# MCX_Isolated_Mezzanine.net
KiCad netlist of a schematic drawn in Altium Designer
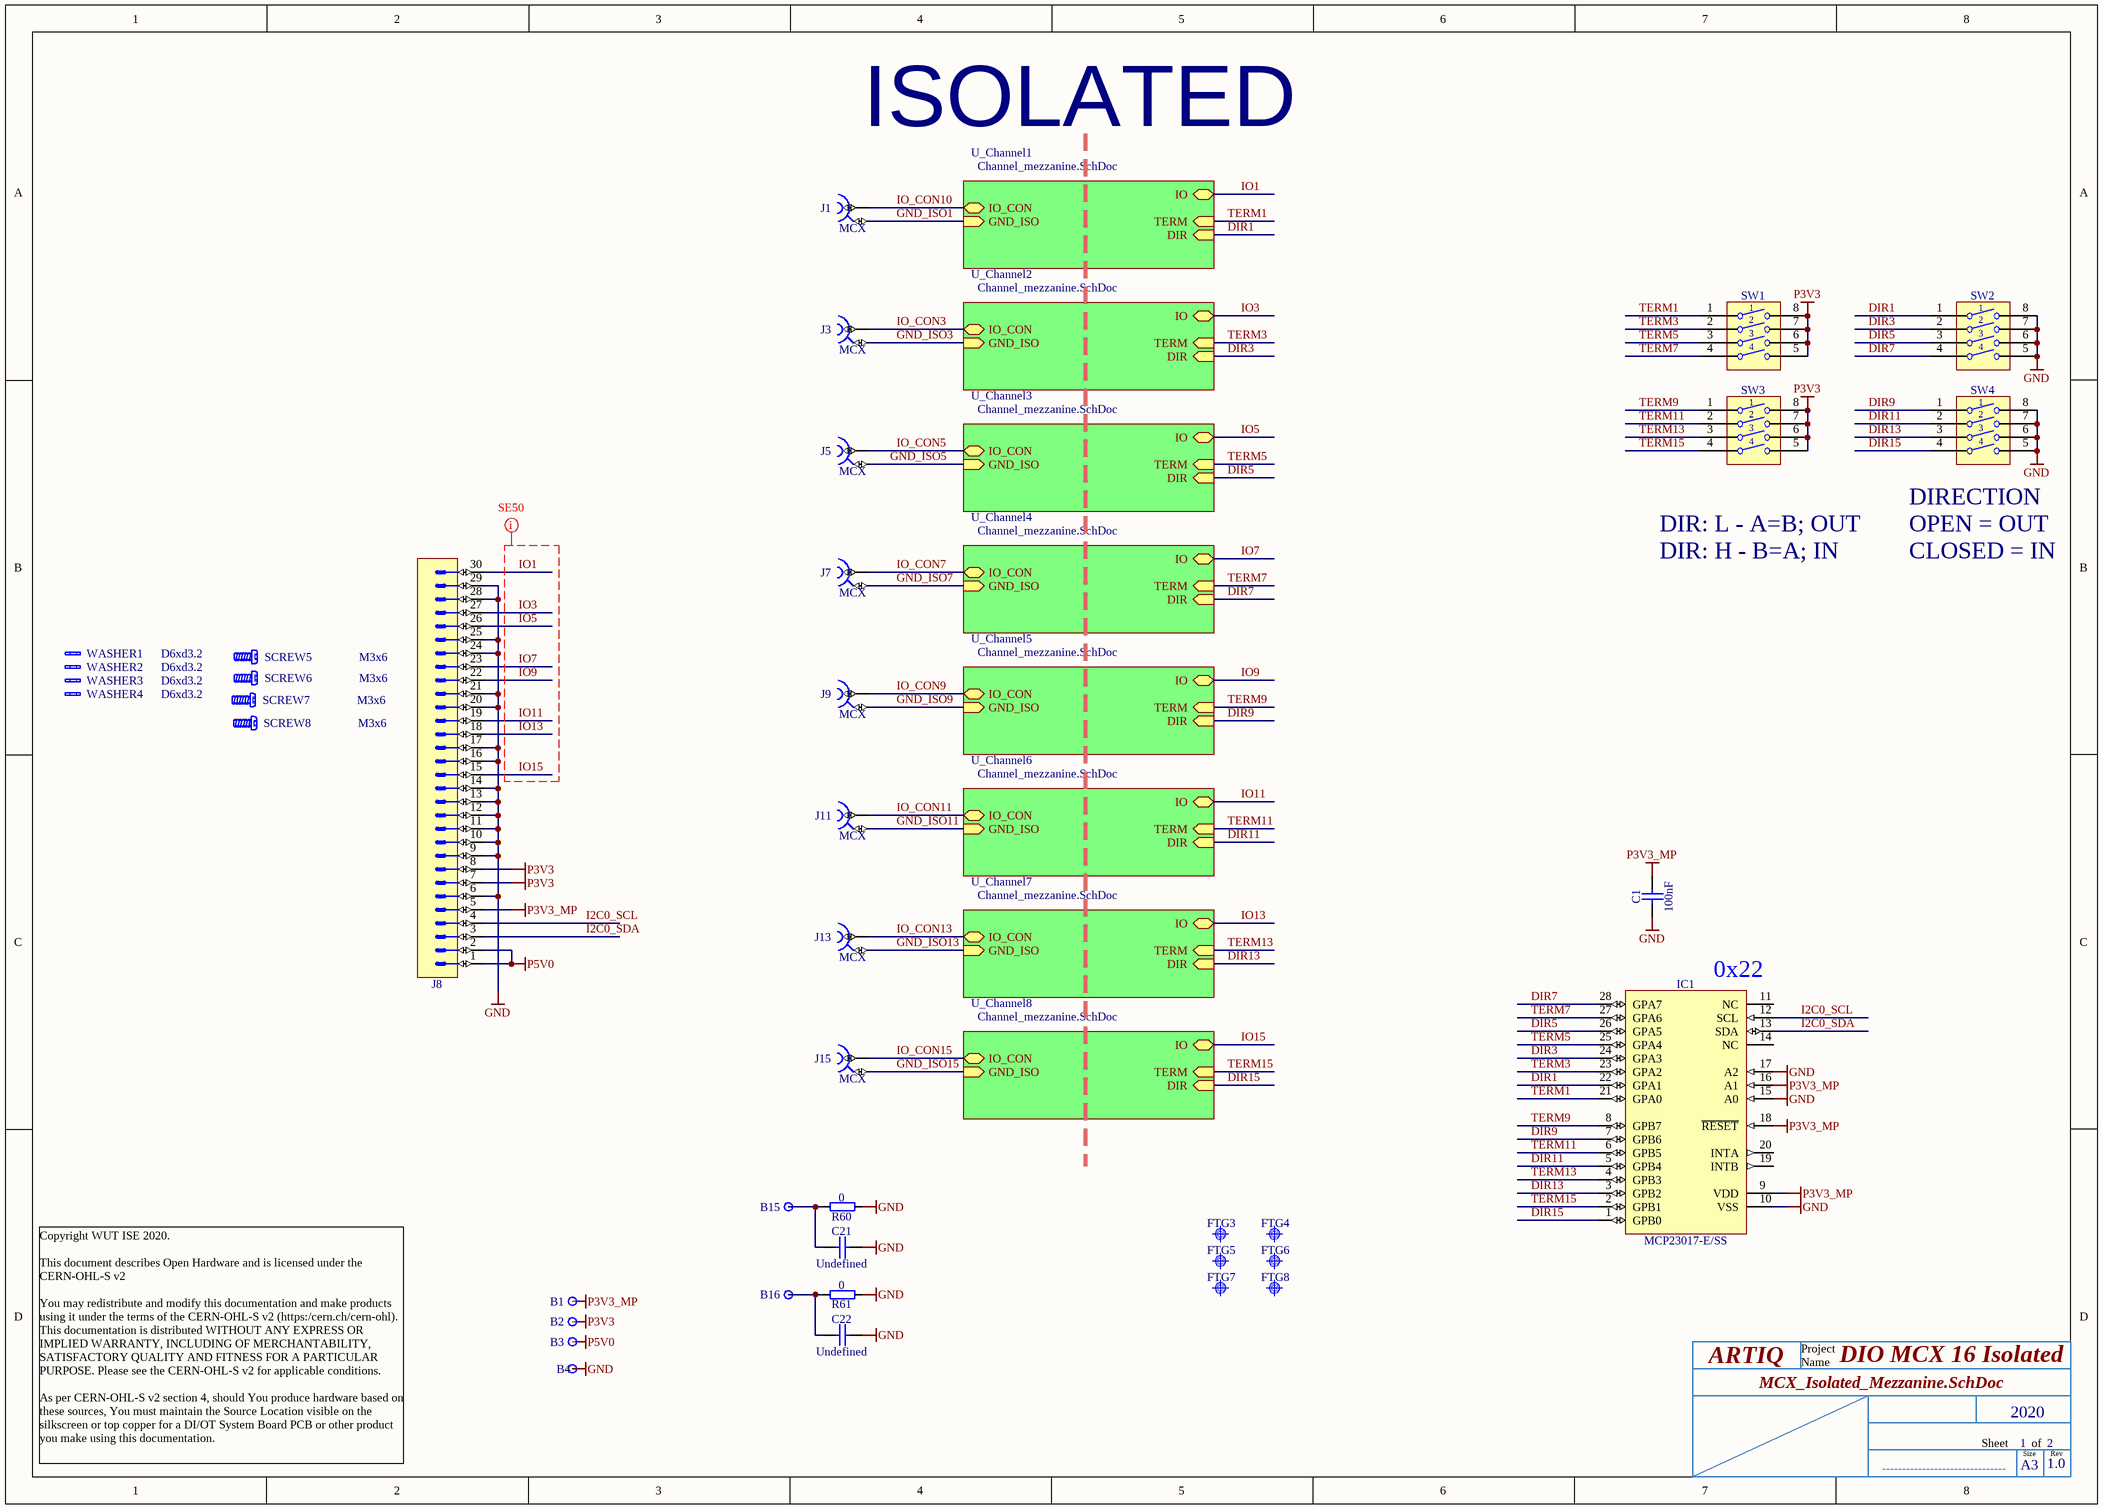
[diagram p0: MCX_Isolated_Mezzanine.SchDoc]

(export (version "E")
  (design (tool "Eeschema 10.0.6"))
  (components
    (comp (ref "B1")
      (value "Plated Hole")
      (footprint "c130h60")
      (description "Single Terminal Socket")
      (fields (field (name "PART NUMBER") "PLATED_HOLE0.6_PAD1.3") (field (name "AUTHOR") "CERN DEM MR"))
      (libsource (lib "Eletro-mechanical") (part "Single Terminal Socket"))
    )
    (comp (ref "B2")
      (value "Plated Hole")
      (footprint "c130h60")
      (description "Single Terminal Socket")
      (fields (field (name "PART NUMBER") "PLATED_HOLE0.6_PAD1.3") (field (name "AUTHOR") "CERN DEM MR"))
      (libsource (lib "Eletro-mechanical") (part "Single Terminal Socket"))
    )
    (comp (ref "B3")
      (value "Plated Hole")
      (footprint "c130h60")
      (description "Single Terminal Socket")
      (fields (field (name "PART NUMBER") "PLATED_HOLE0.6_PAD1.3") (field (name "AUTHOR") "CERN DEM MR"))
      (libsource (lib "Eletro-mechanical") (part "Single Terminal Socket"))
    )
    (comp (ref "B4")
      (value "Plated Hole")
      (footprint "c130h60")
      (description "Single Terminal Socket")
      (fields (field (name "PART NUMBER") "PLATED_HOLE0.6_PAD1.3") (field (name "AUTHOR") "CERN DEM MR"))
      (libsource (lib "Eletro-mechanical") (part "Single Terminal Socket"))
    )
    (comp (ref "B15")
      (value "Plated Hole")
      (footprint "MTG270_500")
      (description "Single Terminal Socket")
      (fields (field (name "PART NUMBER") "PLATED_HOLE2.7_PAD5.0") (field (name "AUTHOR") "CERN DEM JMW"))
      (libsource (lib "Eletro-mechanical") (part "Single Terminal Socket"))
    )
    (comp (ref "B16")
      (value "Plated Hole")
      (footprint "MTG270_500")
      (description "Single Terminal Socket")
      (fields (field (name "PART NUMBER") "PLATED_HOLE2.7_PAD5.0") (field (name "AUTHOR") "CERN DEM JMW"))
      (libsource (lib "Eletro-mechanical") (part "Single Terminal Socket"))
    )
    (comp (ref "C1")
      (value "100nF")
      (footprint "CAPC1005X55N")
      (description "Non-polarised capacitor")
      (fields
        (field (name "PART NUMBER") "CC0402_100NF_50V_10%_X7R")
        (field (name "VOLTAGE") "50V")
        (field (name "AUTHOR") "CERN DEM MR")
      )
      (libsource (lib "Capacitors") (part "Capacitor - non polarized"))
    )
    (comp (ref "C21")
      (value "Undefined")
      (footprint "CAPC2012X135N")
      (description "Non-polarised capacitor")
      (fields (field (name "PART NUMBER") "CC0805_NO-VALUE") (field (name "AUTHOR") "CERN DEM JLC"))
      (libsource (lib "Capacitors") (part "Capacitor - non polarized"))
    )
    (comp (ref "C22")
      (value "Undefined")
      (footprint "CAPC2012X135N")
      (description "Non-polarised capacitor")
      (fields (field (name "PART NUMBER") "CC0805_NO-VALUE") (field (name "AUTHOR") "CERN DEM JLC"))
      (libsource (lib "Capacitors") (part "Capacitor - non polarized"))
    )
    (comp (ref "FTG3")
      (value "Use only in PCB")
      (footprint "FIDUCIAL_TOP_S100-200")
      (description "Fiducial Target")
      (fields (field (name "PART NUMBER") "FIDUCIAL_TARGET_S100-200") (field (name "AUTHOR") "CERN DEM JLC"))
      (libsource (lib "Eletro-mechanical") (part "Fiducial Target"))
    )
    (comp (ref "FTG4")
      (value "Use only in PCB")
      (footprint "FIDUCIAL_TOP_C100-200")
      (description "Fiducial Target")
      (fields (field (name "PART NUMBER") "FIDUCIAL_TARGET_C100-200") (field (name "AUTHOR") "CERN DEM JLC"))
      (libsource (lib "Eletro-mechanical") (part "Fiducial Target"))
    )
    (comp (ref "FTG5")
      (value "Use only in PCB")
      (footprint "FIDUCIAL_TOP_S100-200")
      (description "Fiducial Target")
      (fields (field (name "PART NUMBER") "FIDUCIAL_TARGET_S100-200") (field (name "AUTHOR") "CERN DEM JLC"))
      (libsource (lib "Eletro-mechanical") (part "Fiducial Target"))
    )
    (comp (ref "FTG6")
      (value "Use only in PCB")
      (footprint "FIDUCIAL_TOP_C100-200")
      (description "Fiducial Target")
      (fields (field (name "PART NUMBER") "FIDUCIAL_TARGET_C100-200") (field (name "AUTHOR") "CERN DEM JLC"))
      (libsource (lib "Eletro-mechanical") (part "Fiducial Target"))
    )
    (comp (ref "FTG7")
      (value "Use only in PCB")
      (footprint "FIDUCIAL_TOP_C100-200")
      (description "Fiducial Target")
      (fields (field (name "PART NUMBER") "FIDUCIAL_TARGET_C100-200") (field (name "AUTHOR") "CERN DEM JLC"))
      (libsource (lib "Eletro-mechanical") (part "Fiducial Target"))
    )
    (comp (ref "FTG8")
      (value "Use only in PCB")
      (footprint "FIDUCIAL_TOP_S100-200")
      (description "Fiducial Target")
      (fields (field (name "PART NUMBER") "FIDUCIAL_TARGET_S100-200") (field (name "AUTHOR") "CERN DEM JLC"))
      (libsource (lib "Eletro-mechanical") (part "Fiducial Target"))
    )
    (comp (ref "IC1")
      (value "MCP23017-E/SS")
      (footprint "SOP65P780X200-28N")
      (description "16-bit I/O Port Expander With Serial Interface")
      (fields (field (name "MANUFACTURER") "MICROCHIP TECHNOLOGY") (field (name "AUTHOR") "CERN DEM JLC"))
      (libsource (lib "ICs And Semiconductors") (part "MCP23017-E/SS"))
    )
    (comp (ref "J1")
      (value "MCX")
      (footprint "BEL_133-3701-801")
      (fields
        (field (name "PART NUMBER") "BELFUSE_133-3701-801")
        (field (name "MANUFACTURER") "BEL")
        (field (name "MANUFACTURER PART NUMBER") "133-3701-801")
        (field (name "AUTHOR") "CERN DEM MR")
      )
      (libsource (lib "Connectors") (part "Coax_1Female_1Shield"))
    )
    (comp (ref "J3")
      (value "MCX")
      (footprint "BEL_133-3701-801")
      (fields
        (field (name "PART NUMBER") "BELFUSE_133-3701-801")
        (field (name "MANUFACTURER") "BEL")
        (field (name "MANUFACTURER PART NUMBER") "133-3701-801")
        (field (name "AUTHOR") "CERN DEM MR")
      )
      (libsource (lib "Connectors") (part "Coax_1Female_1Shield"))
    )
    (comp (ref "J5")
      (value "MCX")
      (footprint "BEL_133-3701-801")
      (fields
        (field (name "PART NUMBER") "BELFUSE_133-3701-801")
        (field (name "MANUFACTURER") "BEL")
        (field (name "MANUFACTURER PART NUMBER") "133-3701-801")
        (field (name "AUTHOR") "CERN DEM MR")
      )
      (libsource (lib "Connectors") (part "Coax_1Female_1Shield"))
    )
    (comp (ref "J7")
      (value "MCX")
      (footprint "BEL_133-3701-801")
      (fields
        (field (name "PART NUMBER") "BELFUSE_133-3701-801")
        (field (name "MANUFACTURER") "BEL")
        (field (name "MANUFACTURER PART NUMBER") "133-3701-801")
        (field (name "AUTHOR") "CERN DEM MR")
      )
      (libsource (lib "Connectors") (part "Coax_1Female_1Shield"))
    )
    (comp (ref "J8")
      (value "AMPMODU")
      (footprint "TYCO_1-215307-5")
      (description "Connector 2.54mm, 30 pin female, vertical, 7mm, AMPMODU HV-100/HV-190")
      (fields
        (field (name "PART NUMBER") "TYCO_1-215307-5")
        (field (name "MANUFACTURER") "TYCO ELECTRONICS")
        (field (name "AUTHOR") "GK")
      )
      (libsource (lib "LIBRARY_SCH") (part "CON_2x15_2.54_female_V_mirror"))
    )
    (comp (ref "J9")
      (value "MCX")
      (footprint "BEL_133-3701-801")
      (fields
        (field (name "PART NUMBER") "BELFUSE_133-3701-801")
        (field (name "MANUFACTURER") "BEL")
        (field (name "MANUFACTURER PART NUMBER") "133-3701-801")
        (field (name "AUTHOR") "CERN DEM MR")
      )
      (libsource (lib "Connectors") (part "Coax_1Female_1Shield"))
    )
    (comp (ref "J11")
      (value "MCX")
      (footprint "BEL_133-3701-801")
      (fields
        (field (name "PART NUMBER") "BELFUSE_133-3701-801")
        (field (name "MANUFACTURER") "BEL")
        (field (name "MANUFACTURER PART NUMBER") "133-3701-801")
        (field (name "AUTHOR") "CERN DEM MR")
      )
      (libsource (lib "Connectors") (part "Coax_1Female_1Shield"))
    )
    (comp (ref "J13")
      (value "MCX")
      (footprint "BEL_133-3701-801")
      (fields
        (field (name "PART NUMBER") "BELFUSE_133-3701-801")
        (field (name "MANUFACTURER") "BEL")
        (field (name "MANUFACTURER PART NUMBER") "133-3701-801")
        (field (name "AUTHOR") "CERN DEM MR")
      )
      (libsource (lib "Connectors") (part "Coax_1Female_1Shield"))
    )
    (comp (ref "J15")
      (value "MCX")
      (footprint "BEL_133-3701-801")
      (fields
        (field (name "PART NUMBER") "BELFUSE_133-3701-801")
        (field (name "MANUFACTURER") "BEL")
        (field (name "MANUFACTURER PART NUMBER") "133-3701-801")
        (field (name "AUTHOR") "CERN DEM MR")
      )
      (libsource (lib "Connectors") (part "Coax_1Female_1Shield"))
    )
    (comp (ref "R60")
      (value "0")
      (footprint "RESC1608X55N")
      (description "Resistor")
      (fields
        (field (name "PART NUMBER") "R0603_0R_JUMPER")
        (field (name "MANUFACTURER") "GENERIC")
        (field (name "AUTHOR") "CERN DEM JLC")
      )
      (libsource (lib "Resistors") (part "Resistor"))
    )
    (comp (ref "R61")
      (value "0")
      (footprint "RESC1608X55N")
      (description "Resistor")
      (fields
        (field (name "PART NUMBER") "R0603_0R_JUMPER")
        (field (name "MANUFACTURER") "GENERIC")
        (field (name "AUTHOR") "CERN DEM JLC")
      )
      (libsource (lib "Resistors") (part "Resistor"))
    )
    (comp (ref "SCREW5")
      (value "M3x6")
      (footprint "BOSSARD_BN5687-3061605_v")
      (description "Screw")
      (fields
        (field (name "PART NUMBER") "BOSSARD_BN5687-3061605_v")
        (field (name "MANUFACTURER") "BOSSARD")
        (field (name "AUTHOR") "CERN DEM JLC")
      )
      (libsource (lib "Eletro-mechanical") (part "Screw"))
    )
    (comp (ref "SCREW6")
      (value "M3x6")
      (footprint "BOSSARD_BN5687-3061605_v")
      (description "Screw")
      (fields
        (field (name "PART NUMBER") "BOSSARD_BN5687-3061605_v")
        (field (name "MANUFACTURER") "BOSSARD")
        (field (name "AUTHOR") "CERN DEM JLC")
      )
      (libsource (lib "Eletro-mechanical") (part "Screw"))
    )
    (comp (ref "SCREW7")
      (value "M3x6")
      (footprint "BOSSARD_BN5687-3061605_v")
      (description "Screw")
      (fields
        (field (name "PART NUMBER") "BOSSARD_BN5687-3061605_v")
        (field (name "MANUFACTURER") "BOSSARD")
        (field (name "AUTHOR") "CERN DEM JLC")
      )
      (libsource (lib "Eletro-mechanical") (part "Screw"))
    )
    (comp (ref "SCREW8")
      (value "M3x6")
      (footprint "BOSSARD_BN5687-3061605_v")
      (description "Screw")
      (fields
        (field (name "PART NUMBER") "BOSSARD_BN5687-3061605_v")
        (field (name "MANUFACTURER") "BOSSARD")
        (field (name "AUTHOR") "CERN DEM JLC")
      )
      (libsource (lib "Eletro-mechanical") (part "Screw"))
    )
    (comp (ref "SW1")
      (value "Switch")
      (footprint "SW_OMRON_A6S-4102-H")
      (description "4 Ways SPST DIP Switch")
      (fields
        (field (name "PART NUMBER") "SW_OMRON_A6S-4102-H")
        (field (name "MANUFACTURER") "OMRON")
        (field (name "AUTHOR") "CERN DEM JMW")
      )
      (libsource (lib "Eletro-mechanical") (part "SW 4x SPST DIP Switch"))
    )
    (comp (ref "SW2")
      (value "Switch")
      (footprint "SW_OMRON_A6S-4102-H")
      (description "4 Ways SPST DIP Switch")
      (fields
        (field (name "PART NUMBER") "SW_OMRON_A6S-4102-H")
        (field (name "MANUFACTURER") "OMRON")
        (field (name "AUTHOR") "CERN DEM JMW")
      )
      (libsource (lib "Eletro-mechanical") (part "SW 4x SPST DIP Switch"))
    )
    (comp (ref "SW3")
      (value "Switch")
      (footprint "SW_OMRON_A6S-4102-H")
      (description "4 Ways SPST DIP Switch")
      (fields
        (field (name "PART NUMBER") "SW_OMRON_A6S-4102-H")
        (field (name "MANUFACTURER") "OMRON")
        (field (name "AUTHOR") "CERN DEM JMW")
      )
      (libsource (lib "Eletro-mechanical") (part "SW 4x SPST DIP Switch"))
    )
    (comp (ref "SW4")
      (value "Switch")
      (footprint "SW_OMRON_A6S-4102-H")
      (description "4 Ways SPST DIP Switch")
      (fields
        (field (name "PART NUMBER") "SW_OMRON_A6S-4102-H")
        (field (name "MANUFACTURER") "OMRON")
        (field (name "AUTHOR") "CERN DEM JMW")
      )
      (libsource (lib "Eletro-mechanical") (part "SW 4x SPST DIP Switch"))
    )
    (comp (ref "WASHER1")
      (value "D6xd3.2")
      (footprint "BOSSARD_B3/6/0.3/BN1976_v")
      (description "Washer, M3x0.3x6")
      (fields
        (field (name "PART NUMBER") "BOSSARD_B3/6/0.3/BN1976")
        (field (name "MANUFACTURER") "BOSSARD")
        (field (name "AUTHOR") "GK")
      )
      (libsource (lib "Mechanical") (part "MECH_Washer_M3x0.3x6"))
    )
    (comp (ref "WASHER2")
      (value "D6xd3.2")
      (footprint "BOSSARD_B3/6/0.3/BN1976_v")
      (description "Washer, M3x0.3x6")
      (fields
        (field (name "PART NUMBER") "BOSSARD_B3/6/0.3/BN1976")
        (field (name "MANUFACTURER") "BOSSARD")
        (field (name "AUTHOR") "GK")
      )
      (libsource (lib "Mechanical") (part "MECH_Washer_M3x0.3x6"))
    )
    (comp (ref "WASHER3")
      (value "D6xd3.2")
      (footprint "BOSSARD_B3/6/0.3/BN1976_v")
      (description "Washer, M3x0.3x6")
      (fields
        (field (name "PART NUMBER") "BOSSARD_B3/6/0.3/BN1976")
        (field (name "MANUFACTURER") "BOSSARD")
        (field (name "AUTHOR") "GK")
      )
      (libsource (lib "Mechanical") (part "MECH_Washer_M3x0.3x6"))
    )
    (comp (ref "WASHER4")
      (value "D6xd3.2")
      (footprint "BOSSARD_B3/6/0.3/BN1976_v")
      (description "Washer, M3x0.3x6")
      (fields
        (field (name "PART NUMBER") "BOSSARD_B3/6/0.3/BN1976")
        (field (name "MANUFACTURER") "BOSSARD")
        (field (name "AUTHOR") "GK")
      )
      (libsource (lib "Mechanical") (part "MECH_Washer_M3x0.3x6"))
    )
  )
  (nets
    (net (code "1") (name "/DIR1") (class "Default")
      (node (ref "IC1") (pin "22") (pinfunction "GPA1_22") (pintype "bidirectional"))
      (node (ref "SW2") (pin "1") (pinfunction "1_1") (pintype "passive"))
    )
    (net (code "2") (name "/DIR3") (class "Default")
      (node (ref "IC1") (pin "24") (pinfunction "GPA3_24") (pintype "bidirectional"))
      (node (ref "SW2") (pin "2") (pinfunction "2_2") (pintype "passive"))
    )
    (net (code "3") (name "/DIR5") (class "Default")
      (node (ref "IC1") (pin "26") (pinfunction "GPA5_26") (pintype "bidirectional"))
      (node (ref "SW2") (pin "3") (pinfunction "3_3") (pintype "passive"))
    )
    (net (code "4") (name "/DIR7") (class "Default")
      (node (ref "IC1") (pin "28") (pinfunction "GPA7_28") (pintype "bidirectional"))
      (node (ref "SW2") (pin "4") (pinfunction "4_4") (pintype "passive"))
    )
    (net (code "5") (name "/DIR9") (class "Default")
      (node (ref "IC1") (pin "7") (pinfunction "GPB6_7") (pintype "bidirectional"))
      (node (ref "SW4") (pin "1") (pinfunction "1_1") (pintype "passive"))
    )
    (net (code "6") (name "/DIR11") (class "Default")
      (node (ref "IC1") (pin "5") (pinfunction "GPB4_5") (pintype "bidirectional"))
      (node (ref "SW4") (pin "2") (pinfunction "2_2") (pintype "passive"))
    )
    (net (code "7") (name "/DIR13") (class "Default")
      (node (ref "IC1") (pin "3") (pinfunction "GPB2_3") (pintype "bidirectional"))
      (node (ref "SW4") (pin "3") (pinfunction "3_3") (pintype "passive"))
    )
    (net (code "8") (name "/DIR15") (class "Default")
      (node (ref "IC1") (pin "1") (pinfunction "GPB0_1") (pintype "bidirectional"))
      (node (ref "SW4") (pin "4") (pinfunction "4_4") (pintype "passive"))
    )
    (net (code "9") (name "/GND_ISO1") (class "Default")
      (node (ref "J1") (pin "2") (pinfunction "2_2") (pintype "bidirectional"))
    )
    (net (code "10") (name "/GND_ISO3") (class "Default")
      (node (ref "J3") (pin "2") (pinfunction "2_2") (pintype "bidirectional"))
    )
    (net (code "11") (name "/GND_ISO5") (class "Default")
      (node (ref "J5") (pin "2") (pinfunction "2_2") (pintype "bidirectional"))
    )
    (net (code "12") (name "/GND_ISO7") (class "Default")
      (node (ref "J7") (pin "2") (pinfunction "2_2") (pintype "bidirectional"))
    )
    (net (code "13") (name "/GND_ISO9") (class "Default")
      (node (ref "J9") (pin "2") (pinfunction "2_2") (pintype "bidirectional"))
    )
    (net (code "14") (name "/GND_ISO11") (class "Default")
      (node (ref "J11") (pin "2") (pinfunction "2_2") (pintype "bidirectional"))
    )
    (net (code "15") (name "/GND_ISO13") (class "Default")
      (node (ref "J13") (pin "2") (pinfunction "2_2") (pintype "bidirectional"))
    )
    (net (code "16") (name "/GND_ISO15") (class "Default")
      (node (ref "J15") (pin "2") (pinfunction "2_2") (pintype "bidirectional"))
    )
    (net (code "17") (name "/I2C0_SCL") (class "Default")
      (node (ref "IC1") (pin "12") (pinfunction "SCL_12") (pintype "input"))
      (node (ref "J8") (pin "4") (pinfunction "4_4") (pintype "bidirectional"))
    )
    (net (code "18") (name "/I2C0_SDA") (class "Default")
      (node (ref "IC1") (pin "13") (pinfunction "SDA_13") (pintype "bidirectional"))
      (node (ref "J8") (pin "3") (pinfunction "3_3") (pintype "bidirectional"))
    )
    (net (code "19") (name "/IO1") (class "Default")
      (node (ref "J8") (pin "30") (pinfunction "30_30") (pintype "bidirectional"))
    )
    (net (code "20") (name "/IO3") (class "Default")
      (node (ref "J8") (pin "27") (pinfunction "27_27") (pintype "bidirectional"))
    )
    (net (code "21") (name "/IO5") (class "Default")
      (node (ref "J8") (pin "26") (pinfunction "26_26") (pintype "bidirectional"))
    )
    (net (code "22") (name "/IO7") (class "Default")
      (node (ref "J8") (pin "23") (pinfunction "23_23") (pintype "bidirectional"))
    )
    (net (code "23") (name "/IO9") (class "Default")
      (node (ref "J8") (pin "22") (pinfunction "22_22") (pintype "bidirectional"))
    )
    (net (code "24") (name "/IO11") (class "Default")
      (node (ref "J8") (pin "19") (pinfunction "19_19") (pintype "bidirectional"))
    )
    (net (code "25") (name "/IO13") (class "Default")
      (node (ref "J8") (pin "18") (pinfunction "18_18") (pintype "bidirectional"))
    )
    (net (code "26") (name "/IO15") (class "Default")
      (node (ref "J8") (pin "15") (pinfunction "15_15") (pintype "bidirectional"))
    )
    (net (code "27") (name "/IO_CON3") (class "Default")
      (node (ref "J3") (pin "1") (pinfunction "1_1") (pintype "bidirectional"))
    )
    (net (code "28") (name "/IO_CON5") (class "Default")
      (node (ref "J5") (pin "1") (pinfunction "1_1") (pintype "bidirectional"))
    )
    (net (code "29") (name "/IO_CON7") (class "Default")
      (node (ref "J7") (pin "1") (pinfunction "1_1") (pintype "bidirectional"))
    )
    (net (code "30") (name "/IO_CON9") (class "Default")
      (node (ref "J9") (pin "1") (pinfunction "1_1") (pintype "bidirectional"))
    )
    (net (code "31") (name "/IO_CON10") (class "Default")
      (node (ref "J1") (pin "1") (pinfunction "1_1") (pintype "bidirectional"))
    )
    (net (code "32") (name "/IO_CON11") (class "Default")
      (node (ref "J11") (pin "1") (pinfunction "1_1") (pintype "bidirectional"))
    )
    (net (code "33") (name "/IO_CON13") (class "Default")
      (node (ref "J13") (pin "1") (pinfunction "1_1") (pintype "bidirectional"))
    )
    (net (code "34") (name "/IO_CON15") (class "Default")
      (node (ref "J15") (pin "1") (pinfunction "1_1") (pintype "bidirectional"))
    )
    (net (code "35") (name "/TERM1") (class "Default")
      (node (ref "IC1") (pin "21") (pinfunction "GPA0_21") (pintype "bidirectional"))
      (node (ref "SW1") (pin "1") (pinfunction "1_1") (pintype "passive"))
    )
    (net (code "36") (name "/TERM3") (class "Default")
      (node (ref "IC1") (pin "23") (pinfunction "GPA2_23") (pintype "bidirectional"))
      (node (ref "SW1") (pin "2") (pinfunction "2_2") (pintype "passive"))
    )
    (net (code "37") (name "/TERM5") (class "Default")
      (node (ref "IC1") (pin "25") (pinfunction "GPA4_25") (pintype "bidirectional"))
      (node (ref "SW1") (pin "3") (pinfunction "3_3") (pintype "passive"))
    )
    (net (code "38") (name "/TERM7") (class "Default")
      (node (ref "IC1") (pin "27") (pinfunction "GPA6_27") (pintype "bidirectional"))
      (node (ref "SW1") (pin "4") (pinfunction "4_4") (pintype "passive"))
    )
    (net (code "39") (name "/TERM9") (class "Default")
      (node (ref "IC1") (pin "8") (pinfunction "GPB7_8") (pintype "bidirectional"))
      (node (ref "SW3") (pin "1") (pinfunction "1_1") (pintype "passive"))
    )
    (net (code "40") (name "/TERM11") (class "Default")
      (node (ref "IC1") (pin "6") (pinfunction "GPB5_6") (pintype "bidirectional"))
      (node (ref "SW3") (pin "2") (pinfunction "2_2") (pintype "passive"))
    )
    (net (code "41") (name "/TERM13") (class "Default")
      (node (ref "IC1") (pin "4") (pinfunction "GPB3_4") (pintype "bidirectional"))
      (node (ref "SW3") (pin "3") (pinfunction "3_3") (pintype "passive"))
    )
    (net (code "42") (name "/TERM15") (class "Default")
      (node (ref "IC1") (pin "2") (pinfunction "GPB1_2") (pintype "bidirectional"))
      (node (ref "SW3") (pin "4") (pinfunction "4_4") (pintype "passive"))
    )
    (net (code "43") (name "GND") (class "Default")
      (node (ref "B4") (pin "1") (pinfunction "1_1") (pintype "bidirectional"))
      (node (ref "C1") (pin "1") (pinfunction "1_1") (pintype "passive"))
      (node (ref "C21") (pin "2") (pinfunction "2_2") (pintype "passive"))
      (node (ref "C22") (pin "2") (pinfunction "2_2") (pintype "passive"))
      (node (ref "IC1") (pin "10") (pinfunction "VSS_10") (pintype "power_in"))
      (node (ref "IC1") (pin "15") (pinfunction "A0_15") (pintype "input"))
      (node (ref "IC1") (pin "17") (pinfunction "A2_17") (pintype "input"))
      (node (ref "J8") (pin "10") (pinfunction "10_10") (pintype "bidirectional"))
      (node (ref "J8") (pin "11") (pinfunction "11_11") (pintype "bidirectional"))
      (node (ref "J8") (pin "12") (pinfunction "12_12") (pintype "bidirectional"))
      (node (ref "J8") (pin "13") (pinfunction "13_13") (pintype "bidirectional"))
      (node (ref "J8") (pin "14") (pinfunction "14_14") (pintype "bidirectional"))
      (node (ref "J8") (pin "16") (pinfunction "16_16") (pintype "bidirectional"))
      (node (ref "J8") (pin "17") (pinfunction "17_17") (pintype "bidirectional"))
      (node (ref "J8") (pin "20") (pinfunction "20_20") (pintype "bidirectional"))
      (node (ref "J8") (pin "21") (pinfunction "21_21") (pintype "bidirectional"))
      (node (ref "J8") (pin "24") (pinfunction "24_24") (pintype "bidirectional"))
      (node (ref "J8") (pin "25") (pinfunction "25_25") (pintype "bidirectional"))
      (node (ref "J8") (pin "28") (pinfunction "28_28") (pintype "bidirectional"))
      (node (ref "J8") (pin "29") (pinfunction "29_29") (pintype "bidirectional"))
      (node (ref "J8") (pin "6") (pinfunction "6_6") (pintype "bidirectional"))
      (node (ref "J8") (pin "9") (pinfunction "9_9") (pintype "bidirectional"))
      (node (ref "R60") (pin "1") (pinfunction "1_1") (pintype "passive"))
      (node (ref "R61") (pin "1") (pinfunction "1_1") (pintype "passive"))
      (node (ref "SW2") (pin "5") (pinfunction "5_5") (pintype "passive"))
      (node (ref "SW2") (pin "6") (pinfunction "6_6") (pintype "passive"))
      (node (ref "SW2") (pin "7") (pinfunction "7_7") (pintype "passive"))
      (node (ref "SW2") (pin "8") (pinfunction "8_8") (pintype "passive"))
      (node (ref "SW4") (pin "5") (pinfunction "5_5") (pintype "passive"))
      (node (ref "SW4") (pin "6") (pinfunction "6_6") (pintype "passive"))
      (node (ref "SW4") (pin "7") (pinfunction "7_7") (pintype "passive"))
      (node (ref "SW4") (pin "8") (pinfunction "8_8") (pintype "passive"))
    )
    (net (code "44") (name "Net-(B15-Pad1)") (class "Default")
      (node (ref "B15") (pin "1") (pinfunction "1_1") (pintype "bidirectional"))
      (node (ref "C21") (pin "1") (pinfunction "1_1") (pintype "passive"))
      (node (ref "R60") (pin "2") (pinfunction "2_2") (pintype "passive"))
    )
    (net (code "45") (name "Net-(B16-Pad1)") (class "Default")
      (node (ref "B16") (pin "1") (pinfunction "1_1") (pintype "bidirectional"))
      (node (ref "C22") (pin "1") (pinfunction "1_1") (pintype "passive"))
      (node (ref "R61") (pin "2") (pinfunction "2_2") (pintype "passive"))
    )
    (net (code "46") (name "P3V3") (class "Default")
      (node (ref "B2") (pin "1") (pinfunction "1_1") (pintype "bidirectional"))
      (node (ref "J8") (pin "7") (pinfunction "7_7") (pintype "bidirectional"))
      (node (ref "J8") (pin "8") (pinfunction "8_8") (pintype "bidirectional"))
      (node (ref "SW1") (pin "5") (pinfunction "5_5") (pintype "passive"))
      (node (ref "SW1") (pin "6") (pinfunction "6_6") (pintype "passive"))
      (node (ref "SW1") (pin "7") (pinfunction "7_7") (pintype "passive"))
      (node (ref "SW1") (pin "8") (pinfunction "8_8") (pintype "passive"))
      (node (ref "SW3") (pin "5") (pinfunction "5_5") (pintype "passive"))
      (node (ref "SW3") (pin "6") (pinfunction "6_6") (pintype "passive"))
      (node (ref "SW3") (pin "7") (pinfunction "7_7") (pintype "passive"))
      (node (ref "SW3") (pin "8") (pinfunction "8_8") (pintype "passive"))
    )
    (net (code "47") (name "P3V3_MP") (class "Default")
      (node (ref "B1") (pin "1") (pinfunction "1_1") (pintype "bidirectional"))
      (node (ref "C1") (pin "2") (pinfunction "2_2") (pintype "passive"))
      (node (ref "IC1") (pin "16") (pinfunction "A1_16") (pintype "input"))
      (node (ref "IC1") (pin "18") (pinfunction "~{RESET}_18") (pintype "input"))
      (node (ref "IC1") (pin "9") (pinfunction "VDD_9") (pintype "power_in"))
      (node (ref "J8") (pin "5") (pinfunction "5_5") (pintype "bidirectional"))
    )
    (net (code "48") (name "P5V0") (class "Default")
      (node (ref "B3") (pin "1") (pinfunction "1_1") (pintype "bidirectional"))
      (node (ref "J8") (pin "1") (pinfunction "1_1") (pintype "bidirectional"))
      (node (ref "J8") (pin "2") (pinfunction "2_2") (pintype "bidirectional"))
    )
    (net (code "49") (name "unconnected-(IC1-INTA-Pad20)") (class "Default")
      (node (ref "IC1") (pin "20") (pinfunction "INTA_20") (pintype "output"))
    )
    (net (code "50") (name "unconnected-(IC1-INTB-Pad19)") (class "Default")
      (node (ref "IC1") (pin "19") (pinfunction "INTB_19") (pintype "output"))
    )
    (net (code "51") (name "unconnected-(IC1-NC-Pad11)") (class "Default")
      (node (ref "IC1") (pin "11") (pinfunction "NC_11") (pintype "passive"))
    )
    (net (code "52") (name "unconnected-(IC1-NC-Pad14)") (class "Default")
      (node (ref "IC1") (pin "14") (pinfunction "NC_14") (pintype "passive"))
    )
  )
)
